# main_unit_phase_3.net
KiCad netlist of a schematic drawn in EAGLE
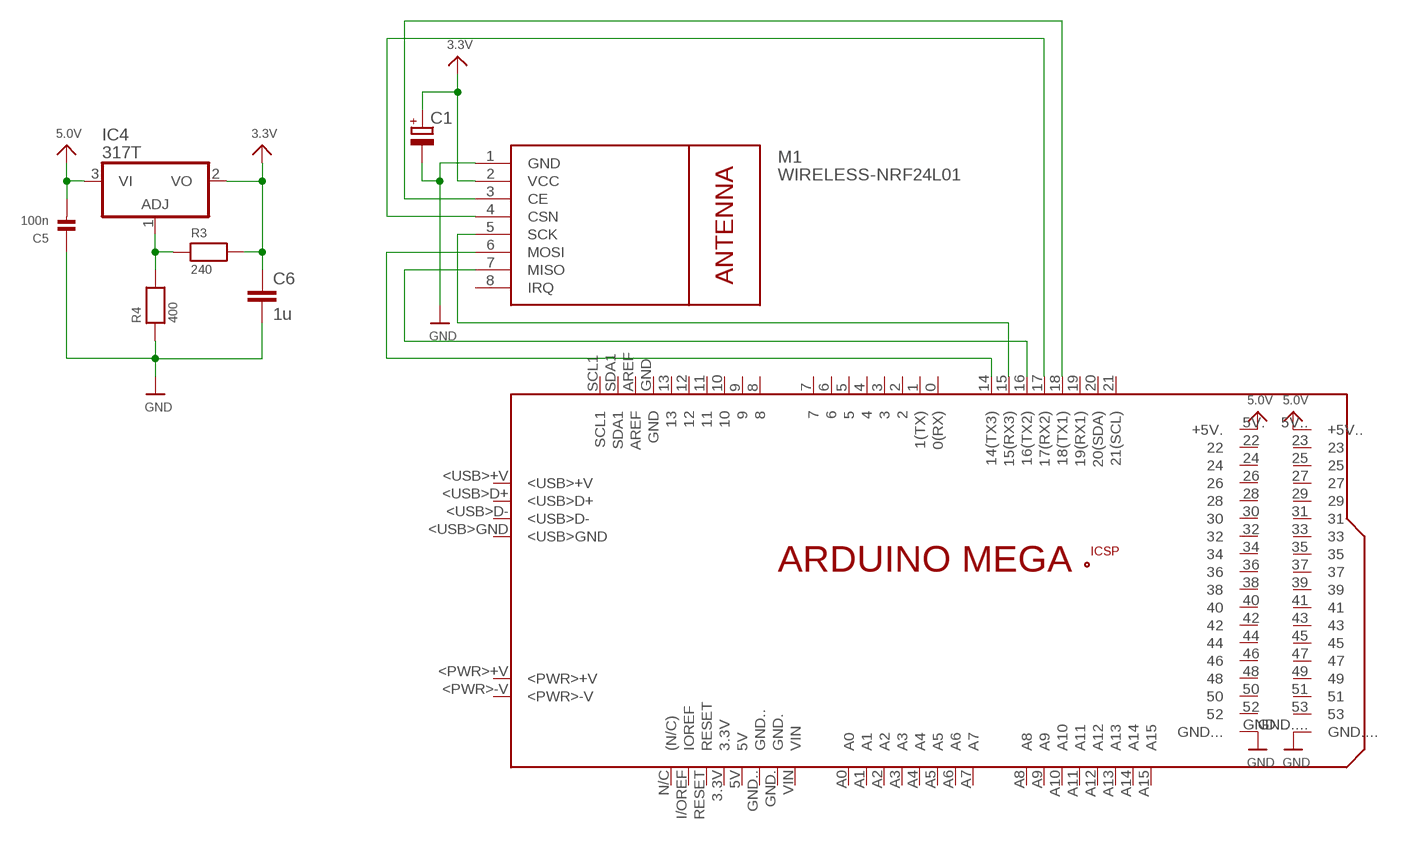
[diagram p0: schematic, sheet 1]

(export (version "E")
  (design (tool "Eeschema 10.0.6"))
  (components
    (comp (ref "C1")
      (value "CPOL-EUE2,5-6E")
      (footprint "eagle-import:E2,5-6E")
      (libsource (lib "eagle-import") (part "CPOL-EUE2,5-6E"))
    )
    (comp (ref "C5")
      (value "100n")
      (footprint "eagle-import:_0603")
      (libsource (lib "eagle-import") (part "CAP_CERAMIC_0603"))
    )
    (comp (ref "C6")
      (value "1u")
      (footprint "eagle-import:C050-035X075")
      (libsource (lib "eagle-import") (part "C-EU050-035X075"))
    )
    (comp (ref "IC4")
      (value "317T")
      (footprint "eagle-import:TO220H")
      (libsource (lib "eagle-import") (part "317T"))
    )
    (comp (ref "M1")
      (value "WIRELESS-NRF24L01")
      (footprint "eagle-import:WIRELESS-NRF24L01")
      (libsource (lib "eagle-import") (part "WIRELESS-NRF24L01"))
    )
    (comp (ref "PCB1")
      (value "ARDUINO_MEGA")
      (footprint "eagle-import:ARDUINO_MEGA")
      (libsource (lib "eagle-import") (part "ARDUINO_MEGA"))
    )
    (comp (ref "R3")
      (value "240")
      (footprint "eagle-import:_0603")
      (libsource (lib "eagle-import") (part "RESISTOR_0603"))
    )
    (comp (ref "R4")
      (value "400")
      (footprint "eagle-import:_0603")
      (libsource (lib "eagle-import") (part "RESISTOR_0603"))
    )
  )
  (nets
    (net (code "1") (name "3.3V") (class "Default")
      (node (ref "C1") (pin "+") (pinfunction "+_+") (pintype "passive"))
      (node (ref "C6") (pin "1") (pinfunction "1_1") (pintype "passive"))
      (node (ref "IC4") (pin "2") (pinfunction "VO_2") (pintype "passive"))
      (node (ref "M1") (pin "2") (pinfunction "VCC_2") (pintype "power_in"))
      (node (ref "R3") (pin "2") (pinfunction "2_2") (pintype "passive"))
    )
    (net (code "2") (name "5.0V") (class "Default")
      (node (ref "C5") (pin "2") (pinfunction "P$2_2") (pintype "passive"))
      (node (ref "IC4") (pin "3") (pinfunction "VI_3") (pintype "input"))
      (node (ref "PCB1") (pin "5V.") (pinfunction "+5V._5V.") (pintype "bidirectional"))
      (node (ref "PCB1") (pin "5V..") (pinfunction "+5V.._5V..") (pintype "bidirectional"))
    )
    (net (code "3") (name "GND") (class "Default")
      (node (ref "C1") (pin "-") (pinfunction "-_-") (pintype "passive"))
      (node (ref "C5") (pin "1") (pinfunction "P$1_1") (pintype "passive"))
      (node (ref "C6") (pin "2") (pinfunction "2_2") (pintype "passive"))
      (node (ref "M1") (pin "1") (pinfunction "GND_1") (pintype "power_in"))
      (node (ref "PCB1") (pin "GND...") (pinfunction "GND..._GND...") (pintype "bidirectional"))
      (node (ref "PCB1") (pin "GND....") (pinfunction "GND...._GND....") (pintype "bidirectional"))
      (node (ref "R4") (pin "1") (pinfunction "1_1") (pintype "passive"))
    )
    (net (code "4") (name "Net-(IC4-ADJ)") (class "Default")
      (node (ref "IC4") (pin "1") (pinfunction "ADJ_1") (pintype "input"))
      (node (ref "R3") (pin "1") (pinfunction "1_1") (pintype "passive"))
      (node (ref "R4") (pin "2") (pinfunction "2_2") (pintype "passive"))
    )
    (net (code "5") (name "Net-(M1-CE)") (class "Default")
      (node (ref "M1") (pin "3") (pinfunction "CE_3") (pintype "bidirectional"))
      (node (ref "PCB1") (pin "18") (pinfunction "18(TX1)_18") (pintype "bidirectional"))
    )
    (net (code "6") (name "Net-(M1-CSN)") (class "Default")
      (node (ref "M1") (pin "4") (pinfunction "CSN_4") (pintype "bidirectional"))
      (node (ref "PCB1") (pin "17") (pinfunction "17(RX2)_17") (pintype "bidirectional"))
    )
    (net (code "7") (name "Net-(M1-MISO)") (class "Default")
      (node (ref "M1") (pin "7") (pinfunction "MISO_7") (pintype "bidirectional"))
      (node (ref "PCB1") (pin "16") (pinfunction "16(TX2)_16") (pintype "bidirectional"))
    )
    (net (code "8") (name "Net-(M1-MOSI)") (class "Default")
      (node (ref "M1") (pin "6") (pinfunction "MOSI_6") (pintype "bidirectional"))
      (node (ref "PCB1") (pin "14") (pinfunction "14(TX3)_14") (pintype "bidirectional"))
    )
    (net (code "9") (name "Net-(M1-SCK)") (class "Default")
      (node (ref "M1") (pin "5") (pinfunction "SCK_5") (pintype "bidirectional"))
      (node (ref "PCB1") (pin "15") (pinfunction "15(RX3)_15") (pintype "bidirectional"))
    )
    (net (code "10") (name "unconnected-(M1-IRQ-Pad8)") (class "Default")
      (node (ref "M1") (pin "8") (pinfunction "IRQ_8") (pintype "bidirectional"))
    )
    (net (code "11") (name "unconnected-(PCB1-(N{slash}C)-PadN{slash}C)") (class "Default")
      (node (ref "PCB1") (pin "N/C") (pinfunction "(N/C)_N/C") (pintype "bidirectional"))
    )
    (net (code "12") (name "unconnected-(PCB1-0(RX)-Pad0)") (class "Default")
      (node (ref "PCB1") (pin "0") (pinfunction "0(RX)_0") (pintype "bidirectional"))
    )
    (net (code "13") (name "unconnected-(PCB1-1(TX)-Pad1)") (class "Default")
      (node (ref "PCB1") (pin "1") (pinfunction "1(TX)_1") (pintype "bidirectional"))
    )
    (net (code "14") (name "unconnected-(PCB1-19(RX1)-Pad19)") (class "Default")
      (node (ref "PCB1") (pin "19") (pinfunction "19(RX1)_19") (pintype "bidirectional"))
    )
    (net (code "15") (name "unconnected-(PCB1-20(SDA)-Pad20)") (class "Default")
      (node (ref "PCB1") (pin "20") (pinfunction "20(SDA)_20") (pintype "bidirectional"))
    )
    (net (code "16") (name "unconnected-(PCB1-21(SCL)-Pad21)") (class "Default")
      (node (ref "PCB1") (pin "21") (pinfunction "21(SCL)_21") (pintype "bidirectional"))
    )
    (net (code "17") (name "unconnected-(PCB1-IOREF-PadI{slash}OREF)") (class "Default")
      (node (ref "PCB1") (pin "I/OREF") (pinfunction "IOREF_I/OREF") (pintype "bidirectional"))
    )
    (net (code "18") (name "unconnected-(PCB1-Pad+5V_)") (class "Default")
      (node (ref "PCB1") (pin "+5V_") (pinfunction "+5V__+5V_") (pintype "bidirectional"))
    )
    (net (code "19") (name "unconnected-(PCB1-Pad2)") (class "Default")
      (node (ref "PCB1") (pin "2") (pinfunction "2_2") (pintype "bidirectional"))
    )
    (net (code "20") (name "unconnected-(PCB1-Pad3)") (class "Default")
      (node (ref "PCB1") (pin "3") (pinfunction "3_3") (pintype "bidirectional"))
    )
    (net (code "21") (name "unconnected-(PCB1-Pad3.3V)") (class "Default")
      (node (ref "PCB1") (pin "3.3V") (pinfunction "3.3V_3.3V") (pintype "bidirectional"))
    )
    (net (code "22") (name "unconnected-(PCB1-Pad4)") (class "Default")
      (node (ref "PCB1") (pin "4") (pinfunction "4_4") (pintype "bidirectional"))
    )
    (net (code "23") (name "unconnected-(PCB1-Pad5)") (class "Default")
      (node (ref "PCB1") (pin "5") (pinfunction "5_5") (pintype "bidirectional"))
    )
    (net (code "24") (name "unconnected-(PCB1-Pad5V)") (class "Default")
      (node (ref "PCB1") (pin "5V") (pinfunction "5V_5V") (pintype "bidirectional"))
    )
    (net (code "25") (name "unconnected-(PCB1-Pad6)") (class "Default")
      (node (ref "PCB1") (pin "6") (pinfunction "6_6") (pintype "bidirectional"))
    )
    (net (code "26") (name "unconnected-(PCB1-Pad7)") (class "Default")
      (node (ref "PCB1") (pin "7") (pinfunction "7_7") (pintype "bidirectional"))
    )
    (net (code "27") (name "unconnected-(PCB1-Pad8)") (class "Default")
      (node (ref "PCB1") (pin "8") (pinfunction "8_8") (pintype "bidirectional"))
    )
    (net (code "28") (name "unconnected-(PCB1-Pad9)") (class "Default")
      (node (ref "PCB1") (pin "9") (pinfunction "9_9") (pintype "bidirectional"))
    )
    (net (code "29") (name "unconnected-(PCB1-Pad10)") (class "Default")
      (node (ref "PCB1") (pin "10") (pinfunction "10_10") (pintype "bidirectional"))
    )
    (net (code "30") (name "unconnected-(PCB1-Pad11)") (class "Default")
      (node (ref "PCB1") (pin "11") (pinfunction "11_11") (pintype "bidirectional"))
    )
    (net (code "31") (name "unconnected-(PCB1-Pad12)") (class "Default")
      (node (ref "PCB1") (pin "12") (pinfunction "12_12") (pintype "bidirectional"))
    )
    (net (code "32") (name "unconnected-(PCB1-Pad13)") (class "Default")
      (node (ref "PCB1") (pin "13") (pinfunction "13_13") (pintype "bidirectional"))
    )
    (net (code "33") (name "unconnected-(PCB1-Pad22)") (class "Default")
      (node (ref "PCB1") (pin "22") (pinfunction "22_22") (pintype "bidirectional"))
    )
    (net (code "34") (name "unconnected-(PCB1-Pad23)") (class "Default")
      (node (ref "PCB1") (pin "23") (pinfunction "23_23") (pintype "bidirectional"))
    )
    (net (code "35") (name "unconnected-(PCB1-Pad24)") (class "Default")
      (node (ref "PCB1") (pin "24") (pinfunction "24_24") (pintype "bidirectional"))
    )
    (net (code "36") (name "unconnected-(PCB1-Pad25)") (class "Default")
      (node (ref "PCB1") (pin "25") (pinfunction "25_25") (pintype "bidirectional"))
    )
    (net (code "37") (name "unconnected-(PCB1-Pad26)") (class "Default")
      (node (ref "PCB1") (pin "26") (pinfunction "26_26") (pintype "bidirectional"))
    )
    (net (code "38") (name "unconnected-(PCB1-Pad27)") (class "Default")
      (node (ref "PCB1") (pin "27") (pinfunction "27_27") (pintype "bidirectional"))
    )
    (net (code "39") (name "unconnected-(PCB1-Pad28)") (class "Default")
      (node (ref "PCB1") (pin "28") (pinfunction "28_28") (pintype "bidirectional"))
    )
    (net (code "40") (name "unconnected-(PCB1-Pad29)") (class "Default")
      (node (ref "PCB1") (pin "29") (pinfunction "29_29") (pintype "bidirectional"))
    )
    (net (code "41") (name "unconnected-(PCB1-Pad30)") (class "Default")
      (node (ref "PCB1") (pin "30") (pinfunction "30_30") (pintype "bidirectional"))
    )
    (net (code "42") (name "unconnected-(PCB1-Pad31)") (class "Default")
      (node (ref "PCB1") (pin "31") (pinfunction "31_31") (pintype "bidirectional"))
    )
    (net (code "43") (name "unconnected-(PCB1-Pad32)") (class "Default")
      (node (ref "PCB1") (pin "32") (pinfunction "32_32") (pintype "bidirectional"))
    )
    (net (code "44") (name "unconnected-(PCB1-Pad33)") (class "Default")
      (node (ref "PCB1") (pin "33") (pinfunction "33_33") (pintype "bidirectional"))
    )
    (net (code "45") (name "unconnected-(PCB1-Pad34)") (class "Default")
      (node (ref "PCB1") (pin "34") (pinfunction "34_34") (pintype "bidirectional"))
    )
    (net (code "46") (name "unconnected-(PCB1-Pad35)") (class "Default")
      (node (ref "PCB1") (pin "35") (pinfunction "35_35") (pintype "bidirectional"))
    )
    (net (code "47") (name "unconnected-(PCB1-Pad36)") (class "Default")
      (node (ref "PCB1") (pin "36") (pinfunction "36_36") (pintype "bidirectional"))
    )
    (net (code "48") (name "unconnected-(PCB1-Pad37)") (class "Default")
      (node (ref "PCB1") (pin "37") (pinfunction "37_37") (pintype "bidirectional"))
    )
    (net (code "49") (name "unconnected-(PCB1-Pad38)") (class "Default")
      (node (ref "PCB1") (pin "38") (pinfunction "38_38") (pintype "bidirectional"))
    )
    (net (code "50") (name "unconnected-(PCB1-Pad39)") (class "Default")
      (node (ref "PCB1") (pin "39") (pinfunction "39_39") (pintype "bidirectional"))
    )
    (net (code "51") (name "unconnected-(PCB1-Pad40)") (class "Default")
      (node (ref "PCB1") (pin "40") (pinfunction "40_40") (pintype "bidirectional"))
    )
    (net (code "52") (name "unconnected-(PCB1-Pad41)") (class "Default")
      (node (ref "PCB1") (pin "41") (pinfunction "41_41") (pintype "bidirectional"))
    )
    (net (code "53") (name "unconnected-(PCB1-Pad42)") (class "Default")
      (node (ref "PCB1") (pin "42") (pinfunction "42_42") (pintype "bidirectional"))
    )
    (net (code "54") (name "unconnected-(PCB1-Pad43)") (class "Default")
      (node (ref "PCB1") (pin "43") (pinfunction "43_43") (pintype "bidirectional"))
    )
    (net (code "55") (name "unconnected-(PCB1-Pad44)") (class "Default")
      (node (ref "PCB1") (pin "44") (pinfunction "44_44") (pintype "bidirectional"))
    )
    (net (code "56") (name "unconnected-(PCB1-Pad45)") (class "Default")
      (node (ref "PCB1") (pin "45") (pinfunction "45_45") (pintype "bidirectional"))
    )
    (net (code "57") (name "unconnected-(PCB1-Pad46)") (class "Default")
      (node (ref "PCB1") (pin "46") (pinfunction "46_46") (pintype "bidirectional"))
    )
    (net (code "58") (name "unconnected-(PCB1-Pad47)") (class "Default")
      (node (ref "PCB1") (pin "47") (pinfunction "47_47") (pintype "bidirectional"))
    )
    (net (code "59") (name "unconnected-(PCB1-Pad48)") (class "Default")
      (node (ref "PCB1") (pin "48") (pinfunction "48_48") (pintype "bidirectional"))
    )
    (net (code "60") (name "unconnected-(PCB1-Pad49)") (class "Default")
      (node (ref "PCB1") (pin "49") (pinfunction "49_49") (pintype "bidirectional"))
    )
    (net (code "61") (name "unconnected-(PCB1-Pad50)") (class "Default")
      (node (ref "PCB1") (pin "50") (pinfunction "50_50") (pintype "bidirectional"))
    )
    (net (code "62") (name "unconnected-(PCB1-Pad51)") (class "Default")
      (node (ref "PCB1") (pin "51") (pinfunction "51_51") (pintype "bidirectional"))
    )
    (net (code "63") (name "unconnected-(PCB1-Pad52)") (class "Default")
      (node (ref "PCB1") (pin "52") (pinfunction "52_52") (pintype "bidirectional"))
    )
    (net (code "64") (name "unconnected-(PCB1-Pad53)") (class "Default")
      (node (ref "PCB1") (pin "53") (pinfunction "53_53") (pintype "bidirectional"))
    )
    (net (code "65") (name "unconnected-(PCB1-Pad<PWR>+V)") (class "Default")
      (node (ref "PCB1") (pin "<PWR>+V") (pinfunction "<PWR>+V_<PWR>+V") (pintype "no_connect"))
    )
    (net (code "66") (name "unconnected-(PCB1-Pad<PWR>-V)") (class "Default")
      (node (ref "PCB1") (pin "<PWR>-V") (pinfunction "<PWR>-V_<PWR>-V") (pintype "no_connect"))
    )
    (net (code "67") (name "unconnected-(PCB1-Pad<USB>+V)") (class "Default")
      (node (ref "PCB1") (pin "<USB>+V") (pinfunction "<USB>+V_<USB>+V") (pintype "no_connect"))
    )
    (net (code "68") (name "unconnected-(PCB1-Pad<USB>D+)") (class "Default")
      (node (ref "PCB1") (pin "<USB>D+") (pinfunction "<USB>D+_<USB>D+") (pintype "no_connect"))
    )
    (net (code "69") (name "unconnected-(PCB1-Pad<USB>D-)") (class "Default")
      (node (ref "PCB1") (pin "<USB>D-") (pinfunction "<USB>D-_<USB>D-") (pintype "no_connect"))
    )
    (net (code "70") (name "unconnected-(PCB1-Pad<USB>GND)") (class "Default")
      (node (ref "PCB1") (pin "<USB>GND") (pinfunction "<USB>GND_<USB>GND") (pintype "no_connect"))
    )
    (net (code "71") (name "unconnected-(PCB1-PadA0)") (class "Default")
      (node (ref "PCB1") (pin "A0") (pinfunction "A0_A0") (pintype "bidirectional"))
    )
    (net (code "72") (name "unconnected-(PCB1-PadA1)") (class "Default")
      (node (ref "PCB1") (pin "A1") (pinfunction "A1_A1") (pintype "bidirectional"))
    )
    (net (code "73") (name "unconnected-(PCB1-PadA2)") (class "Default")
      (node (ref "PCB1") (pin "A2") (pinfunction "A2_A2") (pintype "bidirectional"))
    )
    (net (code "74") (name "unconnected-(PCB1-PadA3)") (class "Default")
      (node (ref "PCB1") (pin "A3") (pinfunction "A3_A3") (pintype "bidirectional"))
    )
    (net (code "75") (name "unconnected-(PCB1-PadA4)") (class "Default")
      (node (ref "PCB1") (pin "A4") (pinfunction "A4_A4") (pintype "bidirectional"))
    )
    (net (code "76") (name "unconnected-(PCB1-PadA5)") (class "Default")
      (node (ref "PCB1") (pin "A5") (pinfunction "A5_A5") (pintype "bidirectional"))
    )
    (net (code "77") (name "unconnected-(PCB1-PadA6)") (class "Default")
      (node (ref "PCB1") (pin "A6") (pinfunction "A6_A6") (pintype "bidirectional"))
    )
    (net (code "78") (name "unconnected-(PCB1-PadA7)") (class "Default")
      (node (ref "PCB1") (pin "A7") (pinfunction "A7_A7") (pintype "bidirectional"))
    )
    (net (code "79") (name "unconnected-(PCB1-PadA8)") (class "Default")
      (node (ref "PCB1") (pin "A8") (pinfunction "A8_A8") (pintype "bidirectional"))
    )
    (net (code "80") (name "unconnected-(PCB1-PadA9)") (class "Default")
      (node (ref "PCB1") (pin "A9") (pinfunction "A9_A9") (pintype "bidirectional"))
    )
    (net (code "81") (name "unconnected-(PCB1-PadA10)") (class "Default")
      (node (ref "PCB1") (pin "A10") (pinfunction "A10_A10") (pintype "bidirectional"))
    )
    (net (code "82") (name "unconnected-(PCB1-PadA11)") (class "Default")
      (node (ref "PCB1") (pin "A11") (pinfunction "A11_A11") (pintype "bidirectional"))
    )
    (net (code "83") (name "unconnected-(PCB1-PadA12)") (class "Default")
      (node (ref "PCB1") (pin "A12") (pinfunction "A12_A12") (pintype "bidirectional"))
    )
    (net (code "84") (name "unconnected-(PCB1-PadA13)") (class "Default")
      (node (ref "PCB1") (pin "A13") (pinfunction "A13_A13") (pintype "bidirectional"))
    )
    (net (code "85") (name "unconnected-(PCB1-PadA14)") (class "Default")
      (node (ref "PCB1") (pin "A14") (pinfunction "A14_A14") (pintype "bidirectional"))
    )
    (net (code "86") (name "unconnected-(PCB1-PadA15)") (class "Default")
      (node (ref "PCB1") (pin "A15") (pinfunction "A15_A15") (pintype "bidirectional"))
    )
    (net (code "87") (name "unconnected-(PCB1-PadAREF)") (class "Default")
      (node (ref "PCB1") (pin "AREF") (pinfunction "AREF_AREF") (pintype "bidirectional"))
    )
    (net (code "88") (name "unconnected-(PCB1-PadGND)") (class "Default")
      (node (ref "PCB1") (pin "GND") (pinfunction "GND_GND") (pintype "bidirectional"))
    )
    (net (code "89") (name "unconnected-(PCB1-PadGND.)") (class "Default")
      (node (ref "PCB1") (pin "GND.") (pinfunction "GND._GND.") (pintype "bidirectional"))
    )
    (net (code "90") (name "unconnected-(PCB1-PadGND..)") (class "Default")
      (node (ref "PCB1") (pin "GND..") (pinfunction "GND.._GND..") (pintype "bidirectional"))
    )
    (net (code "91") (name "unconnected-(PCB1-PadGND__)") (class "Default")
      (node (ref "PCB1") (pin "GND__") (pinfunction "GND___GND__") (pintype "bidirectional"))
    )
    (net (code "92") (name "unconnected-(PCB1-PadMISO)") (class "Default")
      (node (ref "PCB1") (pin "MISO") (pinfunction "MISO_MISO") (pintype "bidirectional"))
    )
    (net (code "93") (name "unconnected-(PCB1-PadMOSI)") (class "Default")
      (node (ref "PCB1") (pin "MOSI") (pinfunction "MOSI_MOSI") (pintype "bidirectional"))
    )
    (net (code "94") (name "unconnected-(PCB1-PadRESET)") (class "Default")
      (node (ref "PCB1") (pin "RESET") (pinfunction "RESET_RESET") (pintype "bidirectional"))
    )
    (net (code "95") (name "unconnected-(PCB1-PadRESET.)") (class "Default")
      (node (ref "PCB1") (pin "RESET.") (pinfunction "RESET._RESET.") (pintype "bidirectional"))
    )
    (net (code "96") (name "unconnected-(PCB1-PadSCK)") (class "Default")
      (node (ref "PCB1") (pin "SCK") (pinfunction "SCK_SCK") (pintype "bidirectional"))
    )
    (net (code "97") (name "unconnected-(PCB1-PadSCL1)") (class "Default")
      (node (ref "PCB1") (pin "SCL1") (pinfunction "SCL1_SCL1") (pintype "bidirectional"))
    )
    (net (code "98") (name "unconnected-(PCB1-PadSDA1)") (class "Default")
      (node (ref "PCB1") (pin "SDA1") (pinfunction "SDA1_SDA1") (pintype "bidirectional"))
    )
    (net (code "99") (name "unconnected-(PCB1-PadVIN)") (class "Default")
      (node (ref "PCB1") (pin "VIN") (pinfunction "VIN_VIN") (pintype "bidirectional"))
    )
  )
)
